# VOLTAGE_INDICATION.net
KiCad netlist of a schematic drawn in Altium Designer
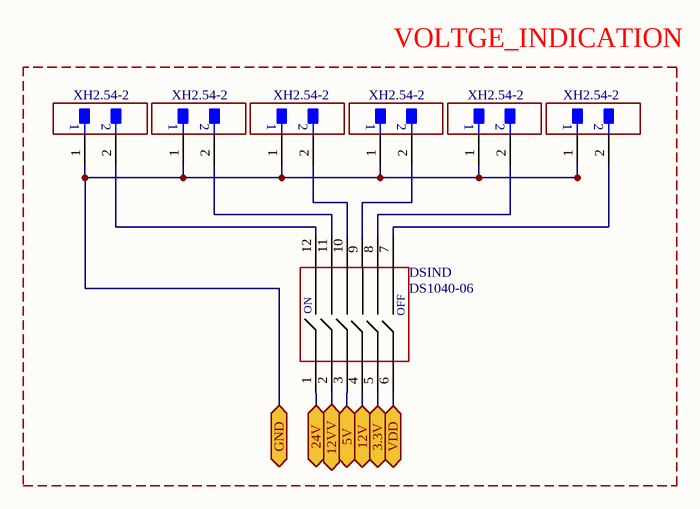
[diagram p0: VOLTAGE_INDICATION.SchDoc]

(export (version "E")
  (design (tool "Eeschema 10.0.6"))
  (components
    (comp (ref "DSIND")
      (value "DS1040-06")
      (footprint "DS1040-06")
      (description "DS1040-06RN")
      (libsource (lib "Components_Robots") (part "DS1040-06"))
    )
    (comp (ref "XH3.3VIND")
      (value "XH2.54-2")
      (footprint "XH2.54-2")
      (description "JST XH2.54-2pin")
      (libsource (lib "Components_Robots") (part "XH2.54-2"))
    )
    (comp (ref "XH5VIND")
      (value "XH2.54-2")
      (footprint "XH2.54-2")
      (description "JST XH2.54-2pin")
      (libsource (lib "Components_Robots") (part "XH2.54-2"))
    )
    (comp (ref "XH12VIND")
      (value "XH2.54-2")
      (footprint "XH2.54-2")
      (description "JST XH2.54-2pin")
      (libsource (lib "Components_Robots") (part "XH2.54-2"))
    )
    (comp (ref "XH12VVIND")
      (value "XH2.54-2")
      (footprint "XH2.54-2")
      (description "JST XH2.54-2pin")
      (libsource (lib "Components_Robots") (part "XH2.54-2"))
    )
    (comp (ref "XH24VIND")
      (value "XH2.54-2")
      (footprint "XH2.54-2")
      (description "JST XH2.54-2pin")
      (libsource (lib "Components_Robots") (part "XH2.54-2"))
    )
    (comp (ref "XHVDDIND")
      (value "XH2.54-2")
      (footprint "XH2.54-2")
      (description "JST XH2.54-2pin")
      (libsource (lib "Components_Robots") (part "XH2.54-2"))
    )
  )
  (nets
    (net (code "1") (name "/3.3V") (class "Default")
      (node (ref "DSIND") (pin "5") (pinfunction "COM_3_5") (pintype "passive"))
    )
    (net (code "2") (name "/5V") (class "Default")
      (node (ref "DSIND") (pin "3") (pinfunction "COM_3_3") (pintype "passive"))
    )
    (net (code "3") (name "/12V") (class "Default")
      (node (ref "DSIND") (pin "4") (pinfunction "COM_3_4") (pintype "passive"))
    )
    (net (code "4") (name "/12VV") (class "Default")
      (node (ref "DSIND") (pin "2") (pinfunction "COM_2_2") (pintype "passive"))
    )
    (net (code "5") (name "/24V") (class "Default")
      (node (ref "DSIND") (pin "1") (pinfunction "COM_1_1") (pintype "passive"))
    )
    (net (code "6") (name "/GND") (class "Default")
      (node (ref "XH12VIND") (pin "1") (pinfunction "1_1") (pintype "passive"))
      (node (ref "XH12VVIND") (pin "1") (pinfunction "1_1") (pintype "passive"))
      (node (ref "XH24VIND") (pin "1") (pinfunction "1_1") (pintype "passive"))
      (node (ref "XH3.3VIND") (pin "1") (pinfunction "1_1") (pintype "passive"))
      (node (ref "XH5VIND") (pin "1") (pinfunction "1_1") (pintype "passive"))
      (node (ref "XHVDDIND") (pin "1") (pinfunction "1_1") (pintype "passive"))
    )
    (net (code "7") (name "/VDD") (class "Default")
      (node (ref "DSIND") (pin "6") (pinfunction "COM_3_6") (pintype "passive"))
    )
    (net (code "8") (name "Net-(DSIND-NO_2-Pad7)") (class "Default")
      (node (ref "DSIND") (pin "7") (pinfunction "NO_2_7") (pintype "passive"))
      (node (ref "XHVDDIND") (pin "2") (pinfunction "2_2") (pintype "passive"))
    )
    (net (code "9") (name "Net-(DSIND-NO_2-Pad8)") (class "Default")
      (node (ref "DSIND") (pin "8") (pinfunction "NO_2_8") (pintype "passive"))
      (node (ref "XH3.3VIND") (pin "2") (pinfunction "2_2") (pintype "passive"))
    )
    (net (code "10") (name "Net-(DSIND-NO_2-Pad9)") (class "Default")
      (node (ref "DSIND") (pin "9") (pinfunction "NO_2_9") (pintype "passive"))
      (node (ref "XH5VIND") (pin "2") (pinfunction "2_2") (pintype "passive"))
    )
    (net (code "11") (name "Net-(DSIND-NO_2-Pad10)") (class "Default")
      (node (ref "DSIND") (pin "10") (pinfunction "NO_2_10") (pintype "passive"))
      (node (ref "XH12VVIND") (pin "2") (pinfunction "2_2") (pintype "passive"))
    )
    (net (code "12") (name "Net-(DSIND-NO_3)") (class "Default")
      (node (ref "DSIND") (pin "11") (pinfunction "NO_3_11") (pintype "passive"))
      (node (ref "XH12VIND") (pin "2") (pinfunction "2_2") (pintype "passive"))
    )
    (net (code "13") (name "Net-(DSIND-NO_4)") (class "Default")
      (node (ref "DSIND") (pin "12") (pinfunction "NO_4_12") (pintype "passive"))
      (node (ref "XH24VIND") (pin "2") (pinfunction "2_2") (pintype "passive"))
    )
  )
)
